# wall-e.net
KiCad netlist of a schematic drawn in EAGLE
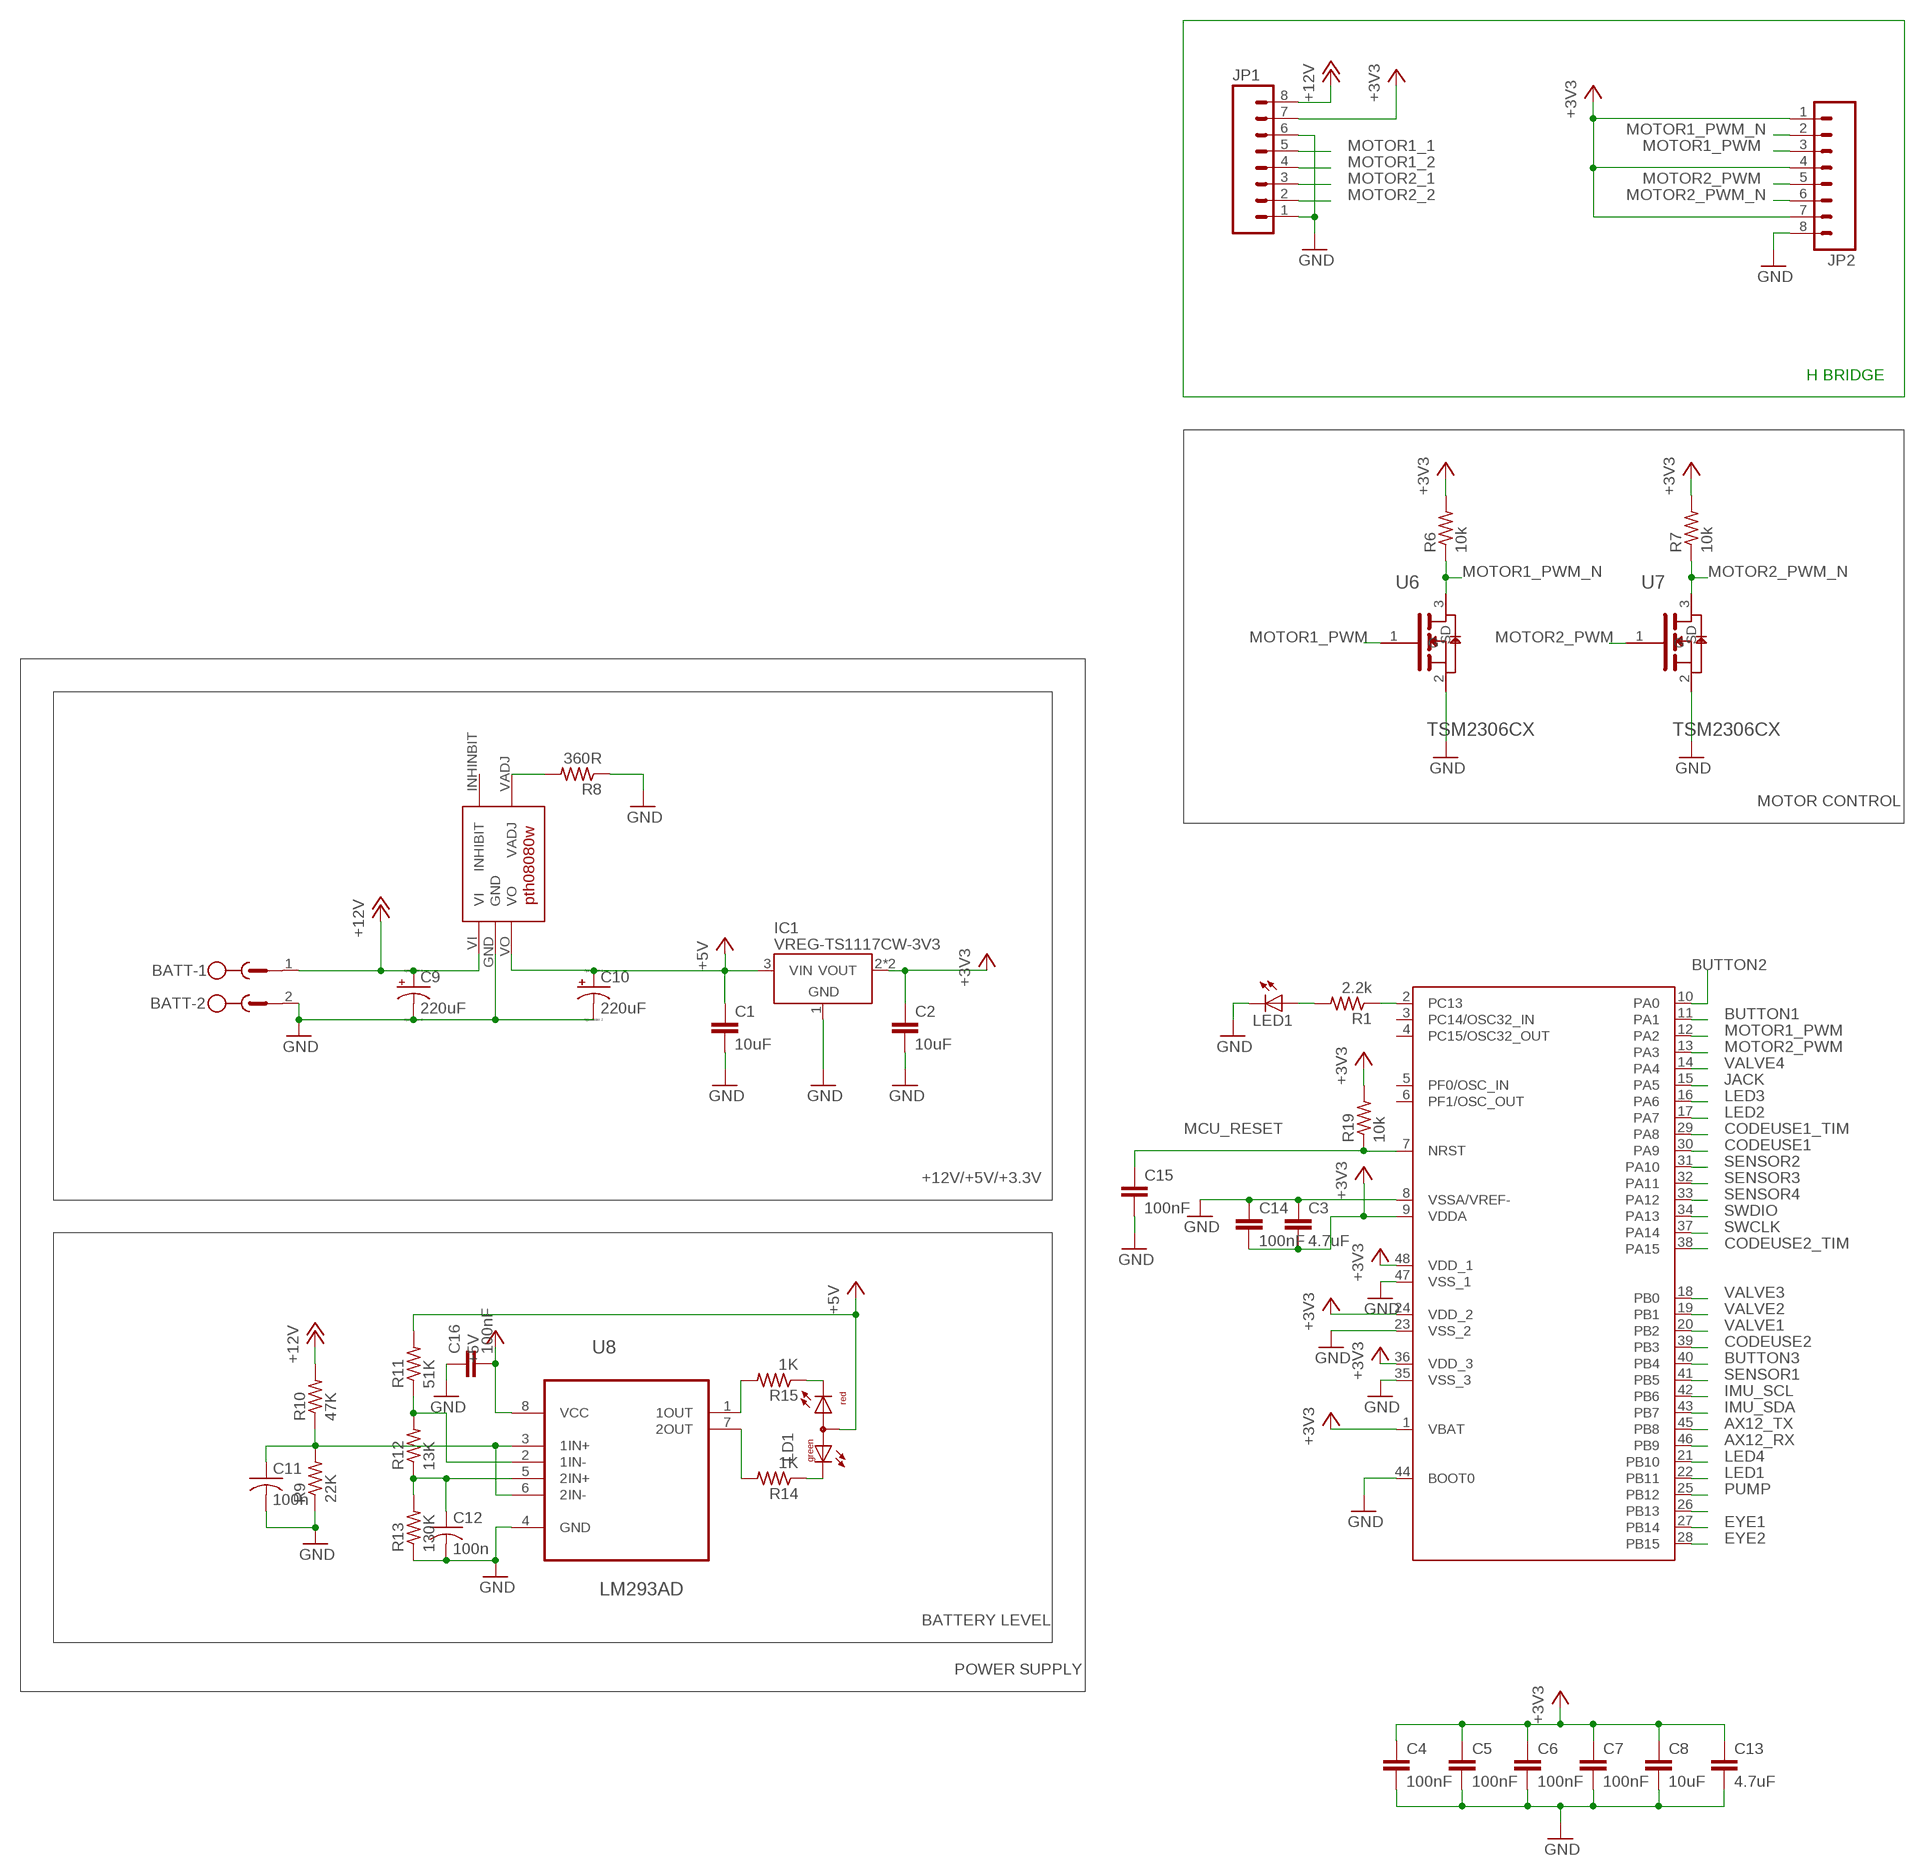
[diagram p0: schematic, sheet 1, part 1 of 2]
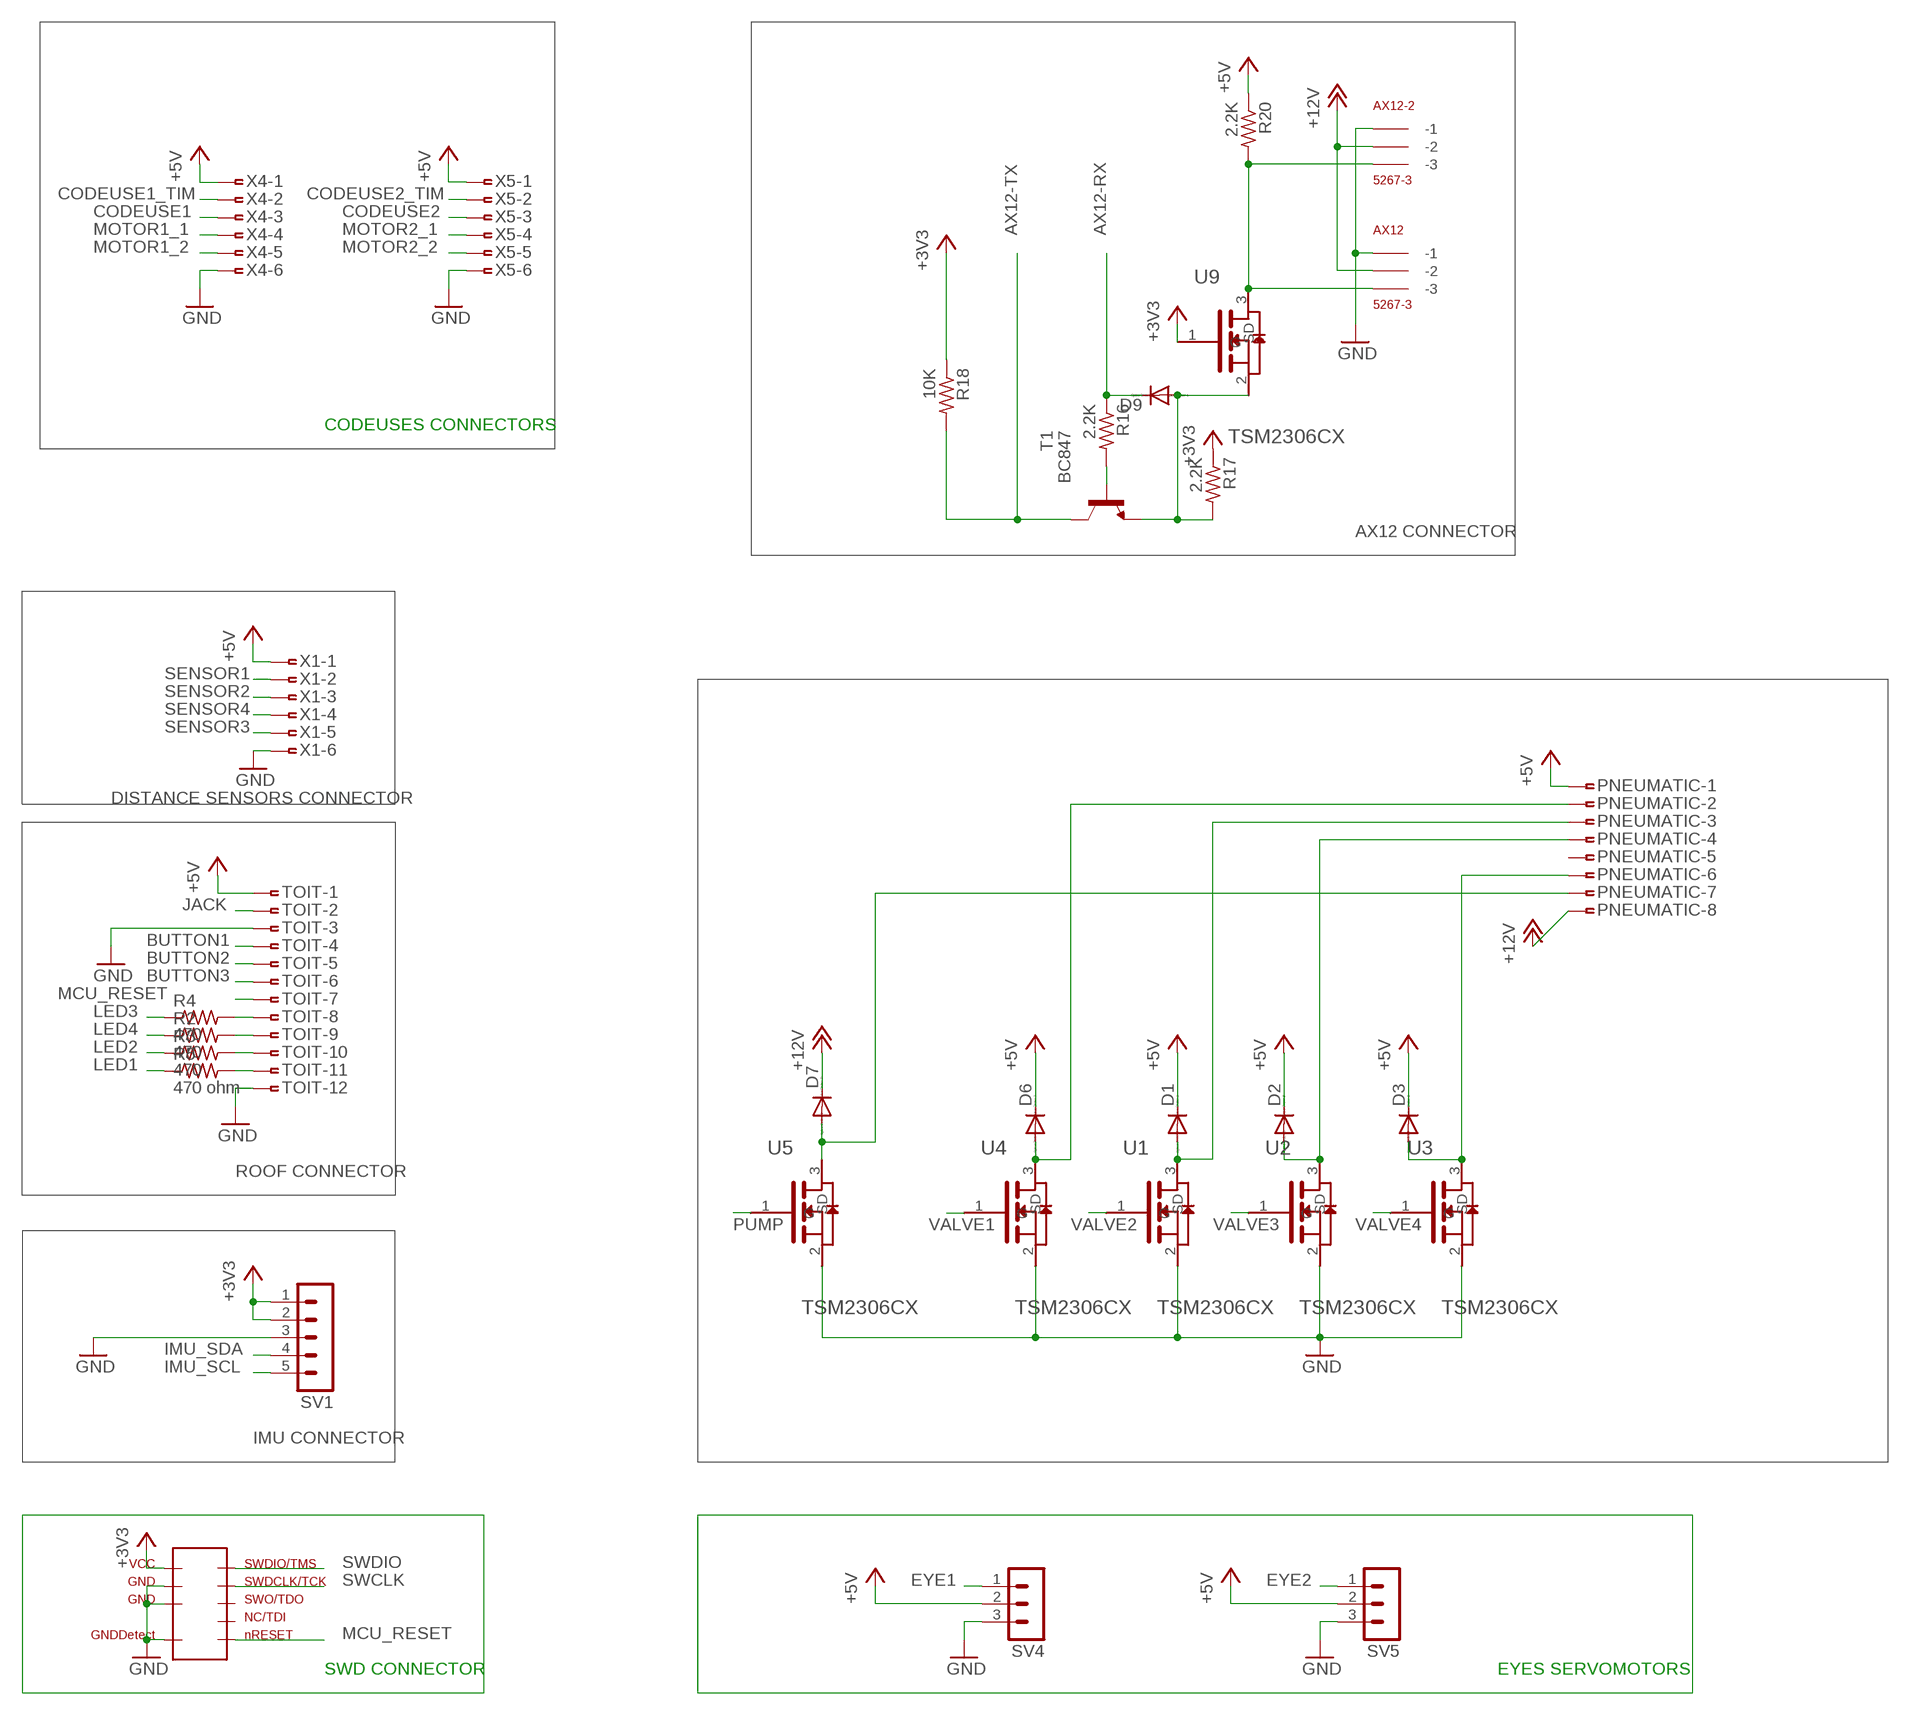
[diagram p1: schematic, sheet 1, part 2 of 2]

(export (version "E")
  (design (tool "Eeschema 10.0.6"))
  (components
    (comp (ref "AX12")
      (value "5267-3")
      (footprint "eagle-import:5267-3")
      (libsource (lib "eagle-import") (part "5267-3"))
    )
    (comp (ref "AX12-2")
      (value "5267-3")
      (footprint "eagle-import:5267-3")
      (libsource (lib "eagle-import") (part "5267-3"))
    )
    (comp (ref "BATT")
      (value "MSTBV2")
      (footprint "eagle-import:MSTBV2")
      (libsource (lib "eagle-import") (part "MSTBV2"))
    )
    (comp (ref "C1")
      (value "10uF")
      (footprint "eagle-import:C0805")
      (libsource (lib "eagle-import") (part "C-EUC0805"))
    )
    (comp (ref "C2")
      (value "10uF")
      (footprint "eagle-import:C0805")
      (libsource (lib "eagle-import") (part "C-EUC0805"))
    )
    (comp (ref "C3")
      (value "4.7uF")
      (footprint "eagle-import:C0805")
      (libsource (lib "eagle-import") (part "C-EUC0805"))
    )
    (comp (ref "C4")
      (value "100nF")
      (footprint "eagle-import:C0805")
      (libsource (lib "eagle-import") (part "C-EUC0805"))
    )
    (comp (ref "C5")
      (value "100nF")
      (footprint "eagle-import:C0805")
      (libsource (lib "eagle-import") (part "C-EUC0805"))
    )
    (comp (ref "C6")
      (value "100nF")
      (footprint "eagle-import:C0805")
      (libsource (lib "eagle-import") (part "C-EUC0805"))
    )
    (comp (ref "C7")
      (value "100nF")
      (footprint "eagle-import:C0805")
      (libsource (lib "eagle-import") (part "C-EUC0805"))
    )
    (comp (ref "C8")
      (value "10uF")
      (footprint "eagle-import:C0805")
      (libsource (lib "eagle-import") (part "C-EUC0805"))
    )
    (comp (ref "C9")
      (value "220uF")
      (footprint "eagle-import:E3,5-8")
      (libsource (lib "eagle-import") (part "CPOL-USE3.5-8"))
    )
    (comp (ref "C10")
      (value "220uF")
      (footprint "eagle-import:E2,5-7")
      (libsource (lib "eagle-import") (part "CPOL-USE2.5-7"))
    )
    (comp (ref "C11")
      (value "100n")
      (footprint "eagle-import:C0805")
      (libsource (lib "eagle-import") (part "C-USC0805"))
    )
    (comp (ref "C12")
      (value "100n")
      (footprint "eagle-import:C0805")
      (libsource (lib "eagle-import") (part "C-USC0805"))
    )
    (comp (ref "C13")
      (value "4.7uF")
      (footprint "eagle-import:C0805")
      (libsource (lib "eagle-import") (part "C-EUC0805"))
    )
    (comp (ref "C14")
      (value "100nF")
      (footprint "eagle-import:C0805")
      (libsource (lib "eagle-import") (part "C-EUC0805"))
    )
    (comp (ref "C15")
      (value "100nF")
      (footprint "eagle-import:C0805")
      (libsource (lib "eagle-import") (part "C-EUC0805"))
    )
    (comp (ref "C16")
      (value "100nF")
      (footprint "eagle-import:C0805")
      (libsource (lib "eagle-import") (part "C-EUC0805"))
    )
    (comp (ref "D1")
      (value "DIODE-SOD323-R")
      (footprint "eagle-import:SOD323-R")
      (libsource (lib "eagle-import") (part "DIODE-SOD323-R"))
    )
    (comp (ref "D2")
      (value "DIODE-SOD323-R")
      (footprint "eagle-import:SOD323-R")
      (libsource (lib "eagle-import") (part "DIODE-SOD323-R"))
    )
    (comp (ref "D3")
      (value "DIODE-SOD323-R")
      (footprint "eagle-import:SOD323-R")
      (libsource (lib "eagle-import") (part "DIODE-SOD323-R"))
    )
    (comp (ref "D6")
      (value "DIODE-SOD323-R")
      (footprint "eagle-import:SOD323-R")
      (libsource (lib "eagle-import") (part "DIODE-SOD323-R"))
    )
    (comp (ref "D7")
      (value "DIODE-SOD323-R")
      (footprint "eagle-import:SOD323-R")
      (libsource (lib "eagle-import") (part "DIODE-SOD323-R"))
    )
    (comp (ref "D9")
      (value "DIODE-SOD523")
      (footprint "eagle-import:SOD523")
      (libsource (lib "eagle-import") (part "DIODE-SOD523"))
    )
    (comp (ref "IC1")
      (value "VREG-TS1117CW-3V3")
      (footprint "eagle-import:SOT223")
      (libsource (lib "eagle-import") (part "VREG-TS1117CW-3V3"))
    )
    (comp (ref "JP1")
      (value "M08LONGPADS")
      (footprint "eagle-import:1X08_LONGPADS")
      (libsource (lib "eagle-import") (part "M08LONGPADS"))
    )
    (comp (ref "JP2")
      (value "M08LONGPADS")
      (footprint "eagle-import:1X08_LONGPADS")
      (libsource (lib "eagle-import") (part "M08LONGPADS"))
    )
    (comp (ref "LD1")
      (value "DUOLED-RG-A")
      (footprint "eagle-import:DUOLED-A-5MM")
      (libsource (lib "eagle-import") (part "DUOLED-RG-A"))
    )
    (comp (ref "LED1")
      (value "LEDCHIP-LED0805")
      (footprint "eagle-import:CHIP-LED0805")
      (libsource (lib "eagle-import") (part "LEDCHIP-LED0805"))
    )
    (comp (ref "PNEUMATIC")
      (value "SMDTOP-8")
      (footprint "eagle-import:SMDTOP8")
      (libsource (lib "eagle-import") (part "SMDTOP-8"))
    )
    (comp (ref "R1")
      (value "2.2k")
      (footprint "eagle-import:R0805")
      (libsource (lib "eagle-import") (part "R-US_R0805"))
    )
    (comp (ref "R2")
      (value "470")
      (footprint "eagle-import:R0805")
      (libsource (lib "eagle-import") (part "R-US_R0805"))
    )
    (comp (ref "R3")
      (value "470")
      (footprint "eagle-import:R0805")
      (libsource (lib "eagle-import") (part "R-US_R0805"))
    )
    (comp (ref "R4")
      (value "470")
      (footprint "eagle-import:R0805")
      (libsource (lib "eagle-import") (part "R-US_R0805"))
    )
    (comp (ref "R5")
      (value "470 ohm")
      (footprint "eagle-import:R0805")
      (libsource (lib "eagle-import") (part "R-US_R0805"))
    )
    (comp (ref "R6")
      (value "10k")
      (footprint "eagle-import:R0805")
      (libsource (lib "eagle-import") (part "R-US_R0805"))
    )
    (comp (ref "R7")
      (value "10k")
      (footprint "eagle-import:R0805")
      (libsource (lib "eagle-import") (part "R-US_R0805"))
    )
    (comp (ref "R8")
      (value "360R")
      (footprint "eagle-import:R0805")
      (libsource (lib "eagle-import") (part "resistor_R-US_R0805"))
    )
    (comp (ref "R9")
      (value "22K")
      (footprint "eagle-import:R0805")
      (libsource (lib "eagle-import") (part "resistor_R-US_R0805"))
    )
    (comp (ref "R10")
      (value "47K")
      (footprint "eagle-import:R0805")
      (libsource (lib "eagle-import") (part "resistor_R-US_R0805"))
    )
    (comp (ref "R11")
      (value "51K")
      (footprint "eagle-import:R0805")
      (libsource (lib "eagle-import") (part "resistor_R-US_R0805"))
    )
    (comp (ref "R12")
      (value "13K")
      (footprint "eagle-import:R0805")
      (libsource (lib "eagle-import") (part "resistor_R-US_R0805"))
    )
    (comp (ref "R13")
      (value "130K")
      (footprint "eagle-import:R0805")
      (libsource (lib "eagle-import") (part "resistor_R-US_R0805"))
    )
    (comp (ref "R14")
      (value "1K")
      (footprint "eagle-import:R0805")
      (libsource (lib "eagle-import") (part "resistor_R-US_R0805"))
    )
    (comp (ref "R15")
      (value "1K")
      (footprint "eagle-import:R0805")
      (libsource (lib "eagle-import") (part "resistor_R-US_R0805"))
    )
    (comp (ref "R16")
      (value "2.2K")
      (footprint "eagle-import:R0805")
      (libsource (lib "eagle-import") (part "resistor_R-US_R0805"))
    )
    (comp (ref "R17")
      (value "2.2K")
      (footprint "eagle-import:R0805")
      (libsource (lib "eagle-import") (part "resistor_R-US_R0805"))
    )
    (comp (ref "R18")
      (value "10K")
      (footprint "eagle-import:R0805")
      (libsource (lib "eagle-import") (part "resistor_R-US_R0805"))
    )
    (comp (ref "R19")
      (value "10k")
      (footprint "eagle-import:R0805")
      (libsource (lib "eagle-import") (part "R-US_R0805"))
    )
    (comp (ref "R20")
      (value "2.2K")
      (footprint "eagle-import:R0805")
      (libsource (lib "eagle-import") (part "resistor_R-US_R0805"))
    )
    (comp (ref "SV1")
      (value "MA05-1")
      (footprint "eagle-import:MA05-1")
      (libsource (lib "eagle-import") (part "MA05-1"))
    )
    (comp (ref "SV4")
      (value "MA03-1")
      (footprint "eagle-import:MA03-1")
      (libsource (lib "eagle-import") (part "MA03-1"))
    )
    (comp (ref "SV5")
      (value "MA03-1")
      (footprint "eagle-import:MA03-1")
      (libsource (lib "eagle-import") (part "MA03-1"))
    )
    (comp (ref "T1")
      (value "BC847")
      (footprint "eagle-import:SOT23")
      (libsource (lib "eagle-import") (part "BC847"))
    )
    (comp (ref "TOIT")
      (value "SMDTOP-12")
      (footprint "eagle-import:SMDTOP12")
      (libsource (lib "eagle-import") (part "SMDTOP-12"))
    )
    (comp (ref "U$1")
      (value "STM32F301C8")
      (footprint "eagle-import:TQFP48")
      (libsource (lib "eagle-import") (part "STM32F301C8"))
    )
    (comp (ref "U$2")
      (value "REGUL_PTH")
      (footprint "eagle-import:REGUL_PTH")
      (libsource (lib "eagle-import") (part "REGUL_PTH"))
    )
    (comp (ref "U$3")
      (value "SWD/JTAG-_PINS")
      (footprint "eagle-import:SAMTEC_SHF-105-01-L-D-SM")
      (libsource (lib "eagle-import") (part "SWD/JTAG-_PINS"))
    )
    (comp (ref "U1")
      (value "TSM2306CX")
      (footprint "eagle-import:SOT95P280X130-3N")
      (libsource (lib "eagle-import") (part "TSM2306CX"))
    )
    (comp (ref "U2")
      (value "TSM2306CX")
      (footprint "eagle-import:SOT95P280X130-3N")
      (libsource (lib "eagle-import") (part "TSM2306CX"))
    )
    (comp (ref "U3")
      (value "TSM2306CX")
      (footprint "eagle-import:SOT95P280X130-3N")
      (libsource (lib "eagle-import") (part "TSM2306CX"))
    )
    (comp (ref "U4")
      (value "TSM2306CX")
      (footprint "eagle-import:SOT95P280X130-3N")
      (libsource (lib "eagle-import") (part "TSM2306CX"))
    )
    (comp (ref "U5")
      (value "TSM2306CX")
      (footprint "eagle-import:SOT95P280X130-3N")
      (libsource (lib "eagle-import") (part "TSM2306CX"))
    )
    (comp (ref "U6")
      (value "TSM2306CX")
      (footprint "eagle-import:SOT95P280X130-3N")
      (libsource (lib "eagle-import") (part "TSM2306CX"))
    )
    (comp (ref "U7")
      (value "TSM2306CX")
      (footprint "eagle-import:SOT95P280X130-3N")
      (libsource (lib "eagle-import") (part "TSM2306CX"))
    )
    (comp (ref "U8")
      (value "LM293AD")
      (footprint "eagle-import:SOIC127P600X175-8N")
      (libsource (lib "eagle-import") (part "LM293AD"))
    )
    (comp (ref "U9")
      (value "TSM2306CX")
      (footprint "eagle-import:SOT95P280X130-3N")
      (libsource (lib "eagle-import") (part "TSM2306CX"))
    )
    (comp (ref "X1")
      (value "SMDTOP-6")
      (footprint "eagle-import:SMDTOP6")
      (libsource (lib "eagle-import") (part "SMDTOP-6"))
    )
    (comp (ref "X4")
      (value "SMDTOP-6")
      (footprint "eagle-import:SMDTOP6")
      (libsource (lib "eagle-import") (part "SMDTOP-6"))
    )
    (comp (ref "X5")
      (value "SMDTOP-6")
      (footprint "eagle-import:SMDTOP6")
      (libsource (lib "eagle-import") (part "SMDTOP-6"))
    )
  )
  (nets
    (net (code "1") (name "+3V3") (class "Default")
      (node (ref "C13") (pin "1") (pinfunction "1_1") (pintype "passive"))
      (node (ref "C14") (pin "2") (pinfunction "2_2") (pintype "passive"))
      (node (ref "C2") (pin "1") (pinfunction "1_1") (pintype "passive"))
      (node (ref "C3") (pin "2") (pinfunction "2_2") (pintype "passive"))
      (node (ref "C4") (pin "1") (pinfunction "1_1") (pintype "passive"))
      (node (ref "C5") (pin "1") (pinfunction "1_1") (pintype "passive"))
      (node (ref "C6") (pin "1") (pinfunction "1_1") (pintype "passive"))
      (node (ref "C7") (pin "1") (pinfunction "1_1") (pintype "passive"))
      (node (ref "C8") (pin "1") (pinfunction "1_1") (pintype "passive"))
      (node (ref "IC1") (pin "2") (pinfunction "VOUT_2") (pintype "power_in"))
      (node (ref "IC1") (pin "4") (pinfunction "VOUT_4") (pintype "power_in"))
      (node (ref "JP1") (pin "7") (pinfunction "7_7") (pintype "passive"))
      (node (ref "JP2") (pin "1") (pinfunction "1_1") (pintype "passive"))
      (node (ref "JP2") (pin "4") (pinfunction "4_4") (pintype "passive"))
      (node (ref "JP2") (pin "7") (pinfunction "7_7") (pintype "passive"))
      (node (ref "R17") (pin "1") (pinfunction "1_1") (pintype "passive"))
      (node (ref "R18") (pin "1") (pinfunction "1_1") (pintype "passive"))
      (node (ref "R19") (pin "2") (pinfunction "2_2") (pintype "passive"))
      (node (ref "R6") (pin "2") (pinfunction "2_2") (pintype "passive"))
      (node (ref "R7") (pin "2") (pinfunction "2_2") (pintype "passive"))
      (node (ref "SV1") (pin "1") (pinfunction "1_1") (pintype "passive"))
      (node (ref "SV1") (pin "2") (pinfunction "2_2") (pintype "passive"))
      (node (ref "U$1") (pin "1") (pinfunction "VBAT_1") (pintype "bidirectional"))
      (node (ref "U$1") (pin "24") (pinfunction "VDD_2_24") (pintype "bidirectional"))
      (node (ref "U$1") (pin "36") (pinfunction "VDD_3_36") (pintype "bidirectional"))
      (node (ref "U$1") (pin "48") (pinfunction "VDD_1_48") (pintype "bidirectional"))
      (node (ref "U$1") (pin "9") (pinfunction "VDDA_9") (pintype "bidirectional"))
      (node (ref "U$3") (pin "P$1") (pinfunction "P$1_P$1") (pintype "bidirectional"))
      (node (ref "U9") (pin "1") (pinfunction "G_1") (pintype "input"))
    )
    (net (code "2") (name "+5V") (class "Default")
      (node (ref "C1") (pin "1") (pinfunction "1_1") (pintype "passive"))
      (node (ref "C10") (pin "+") (pinfunction "+_+") (pintype "passive"))
      (node (ref "C16") (pin "2") (pinfunction "2_2") (pintype "passive"))
      (node (ref "D1") (pin "C") (pinfunction "C_C") (pintype "passive"))
      (node (ref "D2") (pin "C") (pinfunction "C_C") (pintype "passive"))
      (node (ref "D3") (pin "C") (pinfunction "C_C") (pintype "passive"))
      (node (ref "D6") (pin "C") (pinfunction "C_C") (pintype "passive"))
      (node (ref "IC1") (pin "3") (pinfunction "VIN_3") (pintype "power_in"))
      (node (ref "LD1") (pin "A") (pinfunction "A_A") (pintype "passive"))
      (node (ref "PNEUMATIC") (pin "1") (pinfunction "1_1") (pintype "passive"))
      (node (ref "R11") (pin "2") (pinfunction "2_2") (pintype "passive"))
      (node (ref "R20") (pin "1") (pinfunction "1_1") (pintype "passive"))
      (node (ref "SV4") (pin "2") (pinfunction "2_2") (pintype "passive"))
      (node (ref "SV5") (pin "2") (pinfunction "2_2") (pintype "passive"))
      (node (ref "TOIT") (pin "1") (pinfunction "1_1") (pintype "passive"))
      (node (ref "U$2") (pin "VO") (pinfunction "VO_VO") (pintype "bidirectional"))
      (node (ref "U8") (pin "8") (pinfunction "VCC_8") (pintype "power_in"))
      (node (ref "X1") (pin "1") (pinfunction "1_1") (pintype "passive"))
      (node (ref "X4") (pin "1") (pinfunction "1_1") (pintype "passive"))
      (node (ref "X5") (pin "1") (pinfunction "1_1") (pintype "passive"))
    )
    (net (code "3") (name "+12V") (class "Default")
      (node (ref "AX12") (pin "P$2") (pinfunction "-2_P$2") (pintype "bidirectional"))
      (node (ref "AX12-2") (pin "P$2") (pinfunction "-2_P$2") (pintype "bidirectional"))
      (node (ref "BATT") (pin "1") (pinfunction "SK_1") (pintype "passive"))
      (node (ref "C9") (pin "+") (pinfunction "+_+") (pintype "passive"))
      (node (ref "D7") (pin "C") (pinfunction "C_C") (pintype "passive"))
      (node (ref "JP1") (pin "8") (pinfunction "8_8") (pintype "passive"))
      (node (ref "PNEUMATIC") (pin "8") (pinfunction "1_8") (pintype "passive"))
      (node (ref "R10") (pin "2") (pinfunction "2_2") (pintype "passive"))
      (node (ref "U$2") (pin "VI") (pinfunction "VI_VI") (pintype "bidirectional"))
    )
    (net (code "4") (name "/AX12-RX") (class "Default")
      (node (ref "D9") (pin "C") (pinfunction "C_C") (pintype "passive"))
      (node (ref "R16") (pin "1") (pinfunction "1_1") (pintype "passive"))
    )
    (net (code "5") (name "/AX12-TX") (class "Default")
      (node (ref "R18") (pin "2") (pinfunction "2_2") (pintype "passive"))
      (node (ref "T1") (pin "3") (pinfunction "C_3") (pintype "passive"))
    )
    (net (code "6") (name "/AX12_RX") (class "Default")
      (node (ref "U$1") (pin "46") (pinfunction "PB9_46") (pintype "bidirectional"))
    )
    (net (code "7") (name "/AX12_TX") (class "Default")
      (node (ref "U$1") (pin "45") (pinfunction "PB8_45") (pintype "bidirectional"))
    )
    (net (code "8") (name "/BUTTON1") (class "Default")
      (node (ref "TOIT") (pin "4") (pinfunction "1_4") (pintype "passive"))
      (node (ref "U$1") (pin "11") (pinfunction "PA1_11") (pintype "bidirectional"))
    )
    (net (code "9") (name "/BUTTON2") (class "Default")
      (node (ref "TOIT") (pin "5") (pinfunction "1_5") (pintype "passive"))
      (node (ref "U$1") (pin "10") (pinfunction "PA0_10") (pintype "bidirectional"))
    )
    (net (code "10") (name "/BUTTON3") (class "Default")
      (node (ref "TOIT") (pin "6") (pinfunction "1_6") (pintype "passive"))
      (node (ref "U$1") (pin "40") (pinfunction "PB4_40") (pintype "bidirectional"))
    )
    (net (code "11") (name "/CODEUSE1") (class "Default")
      (node (ref "U$1") (pin "30") (pinfunction "PA9_30") (pintype "bidirectional"))
      (node (ref "X4") (pin "3") (pinfunction "1_3") (pintype "passive"))
    )
    (net (code "12") (name "/CODEUSE1_TIM") (class "Default")
      (node (ref "U$1") (pin "29") (pinfunction "PA8_29") (pintype "bidirectional"))
      (node (ref "X4") (pin "2") (pinfunction "1_2") (pintype "passive"))
    )
    (net (code "13") (name "/CODEUSE2") (class "Default")
      (node (ref "U$1") (pin "39") (pinfunction "PB3_39") (pintype "bidirectional"))
      (node (ref "X5") (pin "3") (pinfunction "1_3") (pintype "passive"))
    )
    (net (code "14") (name "/CODEUSE2_TIM") (class "Default")
      (node (ref "U$1") (pin "38") (pinfunction "PA15_38") (pintype "bidirectional"))
      (node (ref "X5") (pin "2") (pinfunction "1_2") (pintype "passive"))
    )
    (net (code "15") (name "/EYE1") (class "Default")
      (node (ref "SV4") (pin "1") (pinfunction "1_1") (pintype "passive"))
      (node (ref "U$1") (pin "27") (pinfunction "PB14_27") (pintype "bidirectional"))
    )
    (net (code "16") (name "/EYE2") (class "Default")
      (node (ref "SV5") (pin "1") (pinfunction "1_1") (pintype "passive"))
      (node (ref "U$1") (pin "28") (pinfunction "PB15_28") (pintype "bidirectional"))
    )
    (net (code "17") (name "/IMU_SCL") (class "Default")
      (node (ref "SV1") (pin "5") (pinfunction "5_5") (pintype "passive"))
      (node (ref "U$1") (pin "42") (pinfunction "PB6_42") (pintype "bidirectional"))
    )
    (net (code "18") (name "/IMU_SDA") (class "Default")
      (node (ref "SV1") (pin "4") (pinfunction "4_4") (pintype "passive"))
      (node (ref "U$1") (pin "43") (pinfunction "PB7_43") (pintype "bidirectional"))
    )
    (net (code "19") (name "/JACK") (class "Default")
      (node (ref "TOIT") (pin "2") (pinfunction "1_2") (pintype "passive"))
      (node (ref "U$1") (pin "15") (pinfunction "PA5_15") (pintype "bidirectional"))
    )
    (net (code "20") (name "/LED1") (class "Default")
      (node (ref "R5") (pin "1") (pinfunction "1_1") (pintype "passive"))
      (node (ref "U$1") (pin "22") (pinfunction "PB11_22") (pintype "bidirectional"))
    )
    (net (code "21") (name "/LED2") (class "Default")
      (node (ref "R3") (pin "1") (pinfunction "1_1") (pintype "passive"))
      (node (ref "U$1") (pin "17") (pinfunction "PA7_17") (pintype "bidirectional"))
    )
    (net (code "22") (name "/LED3") (class "Default")
      (node (ref "R4") (pin "1") (pinfunction "1_1") (pintype "passive"))
      (node (ref "U$1") (pin "16") (pinfunction "PA6_16") (pintype "bidirectional"))
    )
    (net (code "23") (name "/LED4") (class "Default")
      (node (ref "R2") (pin "1") (pinfunction "1_1") (pintype "passive"))
      (node (ref "U$1") (pin "21") (pinfunction "PB10_21") (pintype "bidirectional"))
    )
    (net (code "24") (name "/MCU_RESET") (class "Default")
      (node (ref "C15") (pin "1") (pinfunction "1_1") (pintype "passive"))
      (node (ref "R19") (pin "1") (pinfunction "1_1") (pintype "passive"))
      (node (ref "TOIT") (pin "7") (pinfunction "1_7") (pintype "passive"))
      (node (ref "U$1") (pin "7") (pinfunction "NRST_7") (pintype "bidirectional"))
      (node (ref "U$3") (pin "P$10") (pinfunction "P$10_P$10") (pintype "bidirectional"))
    )
    (net (code "25") (name "/MOTOR1_1") (class "Default")
      (node (ref "JP1") (pin "5") (pinfunction "5_5") (pintype "passive"))
      (node (ref "X4") (pin "4") (pinfunction "1_4") (pintype "passive"))
    )
    (net (code "26") (name "/MOTOR1_2") (class "Default")
      (node (ref "JP1") (pin "4") (pinfunction "4_4") (pintype "passive"))
      (node (ref "X4") (pin "5") (pinfunction "1_5") (pintype "passive"))
    )
    (net (code "27") (name "/MOTOR1_PWM") (class "Default")
      (node (ref "JP2") (pin "3") (pinfunction "3_3") (pintype "passive"))
      (node (ref "U$1") (pin "12") (pinfunction "PA2_12") (pintype "bidirectional"))
      (node (ref "U6") (pin "1") (pinfunction "G_1") (pintype "input"))
    )
    (net (code "28") (name "/MOTOR1_PWM_N") (class "Default")
      (node (ref "JP2") (pin "2") (pinfunction "2_2") (pintype "passive"))
      (node (ref "R6") (pin "1") (pinfunction "1_1") (pintype "passive"))
      (node (ref "U6") (pin "3") (pinfunction "D_3") (pintype "output"))
    )
    (net (code "29") (name "/MOTOR2_1") (class "Default")
      (node (ref "JP1") (pin "3") (pinfunction "3_3") (pintype "passive"))
      (node (ref "X5") (pin "4") (pinfunction "1_4") (pintype "passive"))
    )
    (net (code "30") (name "/MOTOR2_2") (class "Default")
      (node (ref "JP1") (pin "2") (pinfunction "2_2") (pintype "passive"))
      (node (ref "X5") (pin "5") (pinfunction "1_5") (pintype "passive"))
    )
    (net (code "31") (name "/MOTOR2_PWM") (class "Default")
      (node (ref "JP2") (pin "5") (pinfunction "5_5") (pintype "passive"))
      (node (ref "U$1") (pin "13") (pinfunction "PA3_13") (pintype "bidirectional"))
      (node (ref "U7") (pin "1") (pinfunction "G_1") (pintype "input"))
    )
    (net (code "32") (name "/MOTOR2_PWM_N") (class "Default")
      (node (ref "JP2") (pin "6") (pinfunction "6_6") (pintype "passive"))
      (node (ref "R7") (pin "1") (pinfunction "1_1") (pintype "passive"))
      (node (ref "U7") (pin "3") (pinfunction "D_3") (pintype "output"))
    )
    (net (code "33") (name "/PUMP") (class "Default")
      (node (ref "U$1") (pin "25") (pinfunction "PB12_25") (pintype "bidirectional"))
      (node (ref "U5") (pin "1") (pinfunction "G_1") (pintype "input"))
    )
    (net (code "34") (name "/SENSOR1") (class "Default")
      (node (ref "U$1") (pin "41") (pinfunction "PB5_41") (pintype "bidirectional"))
      (node (ref "X1") (pin "2") (pinfunction "1_2") (pintype "passive"))
    )
    (net (code "35") (name "/SENSOR2") (class "Default")
      (node (ref "U$1") (pin "31") (pinfunction "PA10_31") (pintype "bidirectional"))
      (node (ref "X1") (pin "3") (pinfunction "1_3") (pintype "passive"))
    )
    (net (code "36") (name "/SENSOR3") (class "Default")
      (node (ref "U$1") (pin "32") (pinfunction "PA11_32") (pintype "bidirectional"))
      (node (ref "X1") (pin "5") (pinfunction "1_5") (pintype "passive"))
    )
    (net (code "37") (name "/SENSOR4") (class "Default")
      (node (ref "U$1") (pin "33") (pinfunction "PA12_33") (pintype "bidirectional"))
      (node (ref "X1") (pin "4") (pinfunction "1_4") (pintype "passive"))
    )
    (net (code "38") (name "/SWCLK") (class "Default")
      (node (ref "U$1") (pin "37") (pinfunction "PA14_37") (pintype "bidirectional"))
      (node (ref "U$3") (pin "P$4") (pinfunction "P$4_P$4") (pintype "bidirectional"))
    )
    (net (code "39") (name "/SWDIO") (class "Default")
      (node (ref "U$1") (pin "34") (pinfunction "PA13_34") (pintype "bidirectional"))
      (node (ref "U$3") (pin "P$2") (pinfunction "P$2_P$2") (pintype "bidirectional"))
    )
    (net (code "40") (name "/VALVE1") (class "Default")
      (node (ref "U$1") (pin "20") (pinfunction "PB2_20") (pintype "bidirectional"))
      (node (ref "U4") (pin "1") (pinfunction "G_1") (pintype "input"))
    )
    (net (code "41") (name "/VALVE2") (class "Default")
      (node (ref "U$1") (pin "19") (pinfunction "PB1_19") (pintype "bidirectional"))
      (node (ref "U1") (pin "1") (pinfunction "G_1") (pintype "input"))
    )
    (net (code "42") (name "/VALVE3") (class "Default")
      (node (ref "U$1") (pin "18") (pinfunction "PB0_18") (pintype "bidirectional"))
      (node (ref "U2") (pin "1") (pinfunction "G_1") (pintype "input"))
    )
    (net (code "43") (name "/VALVE4") (class "Default")
      (node (ref "U$1") (pin "14") (pinfunction "PA4_14") (pintype "bidirectional"))
      (node (ref "U3") (pin "1") (pinfunction "G_1") (pintype "input"))
    )
    (net (code "44") (name "GND") (class "Default")
      (node (ref "AX12") (pin "P$1") (pinfunction "-1_P$1") (pintype "bidirectional"))
      (node (ref "AX12-2") (pin "P$1") (pinfunction "-1_P$1") (pintype "bidirectional"))
      (node (ref "BATT") (pin "2") (pinfunction "SK_2") (pintype "passive"))
      (node (ref "C1") (pin "2") (pinfunction "2_2") (pintype "passive"))
      (node (ref "C10") (pin "-") (pinfunction "-_-") (pintype "passive"))
      (node (ref "C11") (pin "2") (pinfunction "2_2") (pintype "passive"))
      (node (ref "C12") (pin "2") (pinfunction "2_2") (pintype "passive"))
      (node (ref "C13") (pin "2") (pinfunction "2_2") (pintype "passive"))
      (node (ref "C14") (pin "1") (pinfunction "1_1") (pintype "passive"))
      (node (ref "C15") (pin "2") (pinfunction "2_2") (pintype "passive"))
      (node (ref "C16") (pin "1") (pinfunction "1_1") (pintype "passive"))
      (node (ref "C2") (pin "2") (pinfunction "2_2") (pintype "passive"))
      (node (ref "C3") (pin "1") (pinfunction "1_1") (pintype "passive"))
      (node (ref "C4") (pin "2") (pinfunction "2_2") (pintype "passive"))
      (node (ref "C5") (pin "2") (pinfunction "2_2") (pintype "passive"))
      (node (ref "C6") (pin "2") (pinfunction "2_2") (pintype "passive"))
      (node (ref "C7") (pin "2") (pinfunction "2_2") (pintype "passive"))
      (node (ref "C8") (pin "2") (pinfunction "2_2") (pintype "passive"))
      (node (ref "C9") (pin "-") (pinfunction "-_-") (pintype "passive"))
      (node (ref "IC1") (pin "1") (pinfunction "GND_1") (pintype "power_in"))
      (node (ref "JP1") (pin "1") (pinfunction "1_1") (pintype "passive"))
      (node (ref "JP1") (pin "6") (pinfunction "6_6") (pintype "passive"))
      (node (ref "JP2") (pin "8") (pinfunction "8_8") (pintype "passive"))
      (node (ref "LED1") (pin "C") (pinfunction "C_C") (pintype "passive"))
      (node (ref "R13") (pin "1") (pinfunction "1_1") (pintype "passive"))
      (node (ref "R8") (pin "1") (pinfunction "1_1") (pintype "passive"))
      (node (ref "R9") (pin "1") (pinfunction "1_1") (pintype "passive"))
      (node (ref "SV1") (pin "3") (pinfunction "3_3") (pintype "passive"))
      (node (ref "SV4") (pin "3") (pinfunction "3_3") (pintype "passive"))
      (node (ref "SV5") (pin "3") (pinfunction "3_3") (pintype "passive"))
      (node (ref "TOIT") (pin "12") (pinfunction "1_12") (pintype "passive"))
      (node (ref "TOIT") (pin "3") (pinfunction "1_3") (pintype "passive"))
      (node (ref "U$1") (pin "23") (pinfunction "VSS_2_23") (pintype "bidirectional"))
      (node (ref "U$1") (pin "35") (pinfunction "VSS_3_35") (pintype "bidirectional"))
      (node (ref "U$1") (pin "44") (pinfunction "BOOT0_44") (pintype "bidirectional"))
      (node (ref "U$1") (pin "47") (pinfunction "VSS_1_47") (pintype "bidirectional"))
      (node (ref "U$1") (pin "8") (pinfunction "VSSA/VREF-_8") (pintype "bidirectional"))
      (node (ref "U$2") (pin "GND") (pinfunction "GND_GND") (pintype "bidirectional"))
      (node (ref "U$3") (pin "P$3") (pinfunction "P$3_P$3") (pintype "bidirectional"))
      (node (ref "U$3") (pin "P$5") (pinfunction "P$5_P$5") (pintype "bidirectional"))
      (node (ref "U$3") (pin "P$9") (pinfunction "P$9_P$9") (pintype "bidirectional"))
      (node (ref "U1") (pin "2") (pinfunction "S_2") (pintype "passive"))
      (node (ref "U2") (pin "2") (pinfunction "S_2") (pintype "passive"))
      (node (ref "U3") (pin "2") (pinfunction "S_2") (pintype "passive"))
      (node (ref "U4") (pin "2") (pinfunction "S_2") (pintype "passive"))
      (node (ref "U5") (pin "2") (pinfunction "S_2") (pintype "passive"))
      (node (ref "U6") (pin "2") (pinfunction "S_2") (pintype "passive"))
      (node (ref "U7") (pin "2") (pinfunction "S_2") (pintype "passive"))
      (node (ref "U8") (pin "4") (pinfunction "GND_4") (pintype "passive"))
      (node (ref "X1") (pin "6") (pinfunction "1_6") (pintype "passive"))
      (node (ref "X4") (pin "6") (pinfunction "1_6") (pintype "passive"))
      (node (ref "X5") (pin "6") (pinfunction "1_6") (pintype "passive"))
    )
    (net (code "45") (name "Net-(AX12--3)") (class "Default")
      (node (ref "AX12") (pin "P$3") (pinfunction "-3_P$3") (pintype "bidirectional"))
      (node (ref "AX12-2") (pin "P$3") (pinfunction "-3_P$3") (pintype "bidirectional"))
      (node (ref "R20") (pin "2") (pinfunction "2_2") (pintype "passive"))
      (node (ref "U9") (pin "3") (pinfunction "D_3") (pintype "output"))
    )
    (net (code "46") (name "Net-(LD1-CG)") (class "Default")
      (node (ref "LD1") (pin "CX") (pinfunction "CG_CX") (pintype "passive"))
      (node (ref "R14") (pin "1") (pinfunction "1_1") (pintype "passive"))
    )
    (net (code "47") (name "Net-(LD1-PadCR)") (class "Default")
      (node (ref "LD1") (pin "CR") (pinfunction "CR_CR") (pintype "passive"))
      (node (ref "R15") (pin "1") (pinfunction "1_1") (pintype "passive"))
    )
    (net (code "48") (name "Net-(LED1-PadA)") (class "Default")
      (node (ref "LED1") (pin "A") (pinfunction "A_A") (pintype "passive"))
      (node (ref "R1") (pin "2") (pinfunction "2_2") (pintype "passive"))
    )
    (net (code "49") (name "Net-(PNEUMATICB-1)") (class "Default")
      (node (ref "D6") (pin "A") (pinfunction "A_A") (pintype "passive"))
      (node (ref "PNEUMATIC") (pin "2") (pinfunction "1_2") (pintype "passive"))
      (node (ref "U4") (pin "3") (pinfunction "D_3") (pintype "output"))
    )
    (net (code "50") (name "Net-(PNEUMATICC-1)") (class "Default")
      (node (ref "D1") (pin "A") (pinfunction "A_A") (pintype "passive"))
      (node (ref "PNEUMATIC") (pin "3") (pinfunction "1_3") (pintype "passive"))
      (node (ref "U1") (pin "3") (pinfunction "D_3") (pintype "output"))
    )
    (net (code "51") (name "Net-(PNEUMATICD-1)") (class "Default")
      (node (ref "D2") (pin "A") (pinfunction "A_A") (pintype "passive"))
      (node (ref "PNEUMATIC") (pin "4") (pinfunction "1_4") (pintype "passive"))
      (node (ref "U2") (pin "3") (pinfunction "D_3") (pintype "output"))
    )
    (net (code "52") (name "Net-(PNEUMATICF-1)") (class "Default")
      (node (ref "D3") (pin "A") (pinfunction "A_A") (pintype "passive"))
      (node (ref "PNEUMATIC") (pin "6") (pinfunction "1_6") (pintype "passive"))
      (node (ref "U3") (pin "3") (pinfunction "D_3") (pintype "output"))
    )
    (net (code "53") (name "Net-(PNEUMATICG-1)") (class "Default")
      (node (ref "D7") (pin "A") (pinfunction "A_A") (pintype "passive"))
      (node (ref "PNEUMATIC") (pin "7") (pinfunction "1_7") (pintype "passive"))
      (node (ref "U5") (pin "3") (pinfunction "D_3") (pintype "output"))
    )
    (net (code "54") (name "Net-(R8-Pad2)") (class "Default")
      (node (ref "R8") (pin "2") (pinfunction "2_2") (pintype "passive"))
      (node (ref "U$2") (pin "VADJ") (pinfunction "VADJ_VADJ") (pintype "bidirectional"))
    )
    (net (code "55") (name "Net-(T1-B)") (class "Default")
      (node (ref "R16") (pin "2") (pinfunction "2_2") (pintype "passive"))
      (node (ref "T1") (pin "1") (pinfunction "B_1") (pintype "passive"))
    )
    (net (code "56") (name "Net-(T1-E)") (class "Default")
      (node (ref "D9") (pin "A") (pinfunction "A_A") (pintype "passive"))
      (node (ref "R17") (pin "2") (pinfunction "2_2") (pintype "passive"))
      (node (ref "T1") (pin "2") (pinfunction "E_2") (pintype "passive"))
      (node (ref "U9") (pin "2") (pinfunction "S_2") (pintype "passive"))
    )
    (net (code "57") (name "Net-(TOITB-1)") (class "Default")
      (node (ref "R3") (pin "2") (pinfunction "2_2") (pintype "passive"))
      (node (ref "TOIT") (pin "10") (pinfunction "1_10") (pintype "passive"))
    )
    (net (code "58") (name "Net-(TOITC-1)") (class "Default")
      (node (ref "R5") (pin "2") (pinfunction "2_2") (pintype "passive"))
      (node (ref "TOIT") (pin "11") (pinfunction "1_11") (pintype "passive"))
    )
    (net (code "59") (name "Net-(TOITK-1)") (class "Default")
      (node (ref "R4") (pin "2") (pinfunction "2_2") (pintype "passive"))
      (node (ref "TOIT") (pin "8") (pinfunction "1_8") (pintype "passive"))
    )
    (net (code "60") (name "Net-(TOITL-1)") (class "Default")
      (node (ref "R2") (pin "2") (pinfunction "2_2") (pintype "passive"))
      (node (ref "TOIT") (pin "9") (pinfunction "1_9") (pintype "passive"))
    )
    (net (code "61") (name "Net-(U$1-PC13)") (class "Default")
      (node (ref "R1") (pin "1") (pinfunction "1_1") (pintype "passive"))
      (node (ref "U$1") (pin "2") (pinfunction "PC13_2") (pintype "bidirectional"))
    )
    (net (code "62") (name "Net-(U8-1IN+)") (class "Default")
      (node (ref "C11") (pin "1") (pinfunction "1_1") (pintype "passive"))
      (node (ref "R10") (pin "1") (pinfunction "1_1") (pintype "passive"))
      (node (ref "R9") (pin "2") (pinfunction "2_2") (pintype "passive"))
      (node (ref "U8") (pin "3") (pinfunction "1IN+_3") (pintype "input"))
      (node (ref "U8") (pin "6") (pinfunction "2IN-_6") (pintype "input"))
    )
    (net (code "63") (name "Net-(U8-1IN-)") (class "Default")
      (node (ref "R11") (pin "1") (pinfunction "1_1") (pintype "passive"))
      (node (ref "R12") (pin "2") (pinfunction "2_2") (pintype "passive"))
      (node (ref "U8") (pin "2") (pinfunction "1IN-_2") (pintype "input"))
    )
    (net (code "64") (name "Net-(U8-1OUT)") (class "Default")
      (node (ref "R15") (pin "2") (pinfunction "2_2") (pintype "passive"))
      (node (ref "U8") (pin "1") (pinfunction "1OUT_1") (pintype "output"))
    )
    (net (code "65") (name "Net-(U8-2IN+)") (class "Default")
      (node (ref "C12") (pin "1") (pinfunction "1_1") (pintype "passive"))
      (node (ref "R12") (pin "1") (pinfunction "1_1") (pintype "passive"))
      (node (ref "R13") (pin "2") (pinfunction "2_2") (pintype "passive"))
      (node (ref "U8") (pin "5") (pinfunction "2IN+_5") (pintype "input"))
    )
    (net (code "66") (name "Net-(U8-2OUT)") (class "Default")
      (node (ref "R14") (pin "2") (pinfunction "2_2") (pintype "passive"))
      (node (ref "U8") (pin "7") (pinfunction "2OUT_7") (pintype "output"))
    )
    (net (code "67") (name "unconnected-(PNEUMATICE-1-Pad5)") (class "Default")
      (node (ref "PNEUMATIC") (pin "5") (pinfunction "1_5") (pintype "passive"))
    )
    (net (code "68") (name "unconnected-(U$1-PB13-Pad26)") (class "Default")
      (node (ref "U$1") (pin "26") (pinfunction "PB13_26") (pintype "bidirectional"))
    )
    (net (code "69") (name "unconnected-(U$1-PC14{slash}OSC32_IN-Pad3)") (class "Default")
      (node (ref "U$1") (pin "3") (pinfunction "PC14/OSC32_IN_3") (pintype "bidirectional"))
    )
    (net (code "70") (name "unconnected-(U$1-PC15{slash}OSC32_OUT-Pad4)") (class "Default")
      (node (ref "U$1") (pin "4") (pinfunction "PC15/OSC32_OUT_4") (pintype "bidirectional"))
    )
    (net (code "71") (name "unconnected-(U$1-PF0{slash}OSC_IN-Pad5)") (class "Default")
      (node (ref "U$1") (pin "5") (pinfunction "PF0/OSC_IN_5") (pintype "bidirectional"))
    )
    (net (code "72") (name "unconnected-(U$1-PF1{slash}OSC_OUT-Pad6)") (class "Default")
      (node (ref "U$1") (pin "6") (pinfunction "PF1/OSC_OUT_6") (pintype "bidirectional"))
    )
    (net (code "73") (name "unconnected-(U$2-INHIBIT-PadINHINBIT)") (class "Default")
      (node (ref "U$2") (pin "INHINBIT") (pinfunction "INHIBIT_INHINBIT") (pintype "bidirectional"))
    )
    (net (code "74") (name "unconnected-(U$3-PadP$6)") (class "Default")
      (node (ref "U$3") (pin "P$6") (pinfunction "P$6_P$6") (pintype "bidirectional"))
    )
    (net (code "75") (name "unconnected-(U$3-PadP$8)") (class "Default")
      (node (ref "U$3") (pin "P$8") (pinfunction "P$8_P$8") (pintype "bidirectional"))
    )
  )
)
